# 2CAN.net
KiCad netlist of a schematic drawn in EAGLE
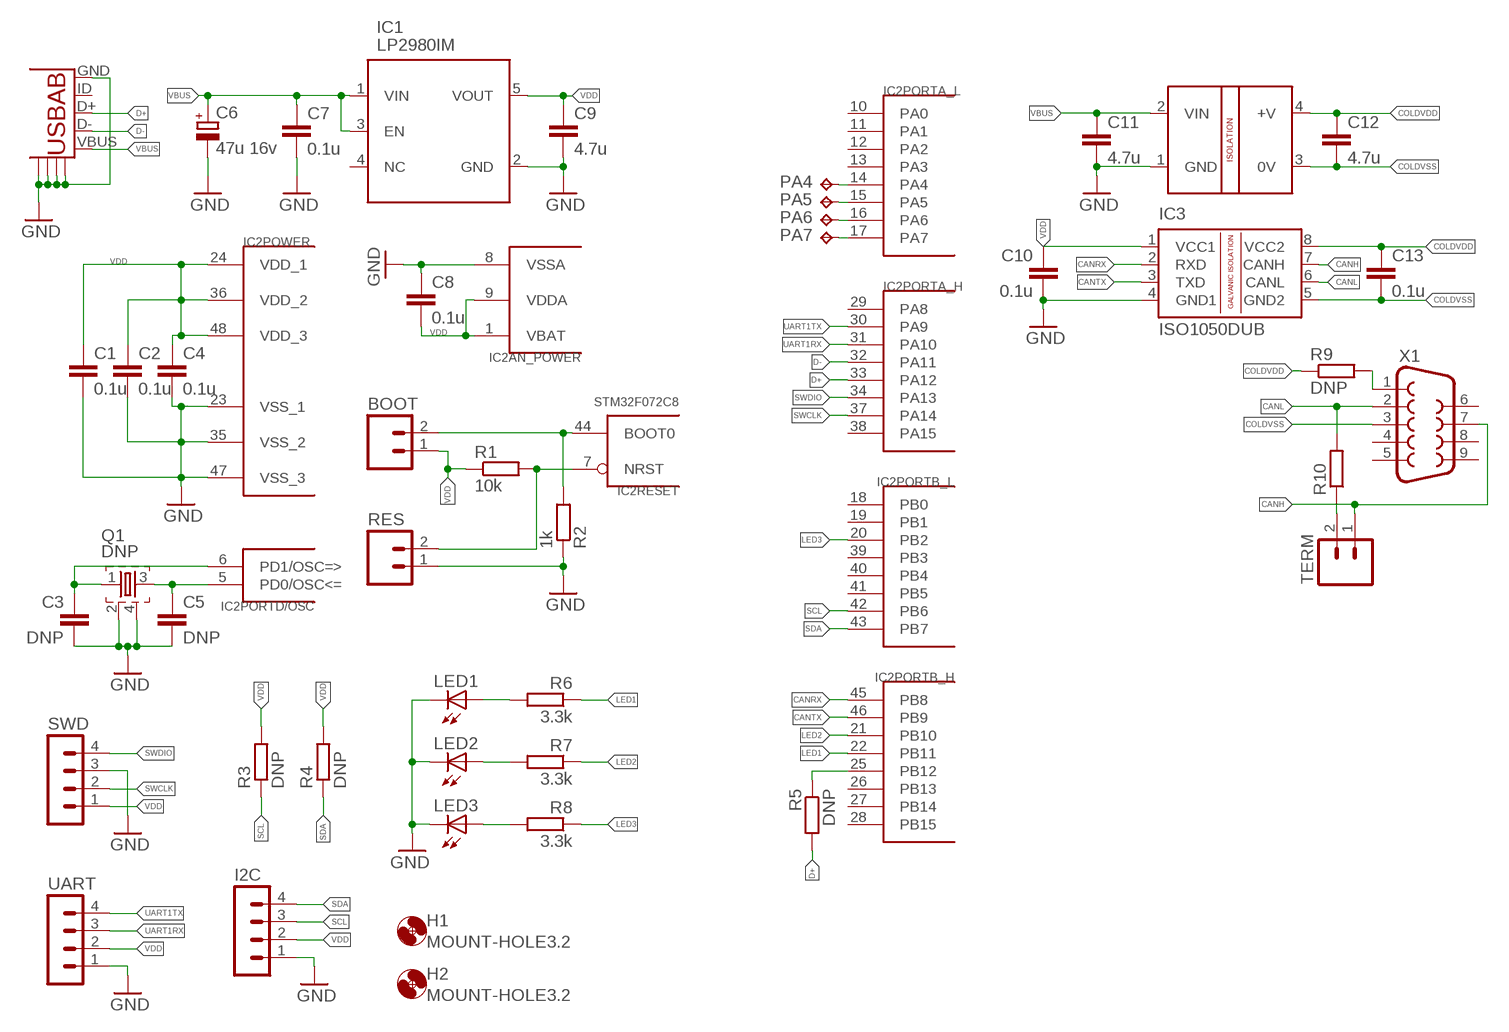
[diagram p0: schematic, sheet 1]

(export (version "E")
  (design (tool "Eeschema 10.0.6"))
  (components
    (comp (ref "BOOT")
      (value "M02PTH")
      (footprint "eagle-import:1X02")
      (libsource (lib "eagle-import") (part "M02PTH"))
    )
    (comp (ref "C1")
      (value "0.1u")
      (footprint "eagle-import:C0603")
      (libsource (lib "eagle-import") (part "C-EUC0603"))
    )
    (comp (ref "C2")
      (value "0.1u")
      (footprint "eagle-import:C0603")
      (libsource (lib "eagle-import") (part "C-EUC0603"))
    )
    (comp (ref "C3")
      (value "DNP")
      (footprint "eagle-import:C0603")
      (libsource (lib "eagle-import") (part "C-EUC0603"))
    )
    (comp (ref "C4")
      (value "0.1u")
      (footprint "eagle-import:C0603")
      (libsource (lib "eagle-import") (part "C-EUC0603"))
    )
    (comp (ref "C5")
      (value "DNP")
      (footprint "eagle-import:C0603")
      (libsource (lib "eagle-import") (part "C-EUC0603"))
    )
    (comp (ref "C6")
      (value "47u 16v")
      (footprint "eagle-import:E2-5")
      (libsource (lib "eagle-import") (part "CPOL-EUE2-5"))
    )
    (comp (ref "C7")
      (value "0.1u")
      (footprint "eagle-import:C0603")
      (libsource (lib "eagle-import") (part "C-EUC0603"))
    )
    (comp (ref "C8")
      (value "0.1u")
      (footprint "eagle-import:C0603")
      (libsource (lib "eagle-import") (part "C-EUC0603"))
    )
    (comp (ref "C9")
      (value "4.7u")
      (footprint "eagle-import:C0805")
      (libsource (lib "eagle-import") (part "C-EUC0805"))
    )
    (comp (ref "C10")
      (value "0.1u")
      (footprint "eagle-import:C0603")
      (libsource (lib "eagle-import") (part "C-EUC0603"))
    )
    (comp (ref "C11")
      (value "4.7u")
      (footprint "eagle-import:C0805")
      (libsource (lib "eagle-import") (part "C-EUC0805"))
    )
    (comp (ref "C12")
      (value "4.7u")
      (footprint "eagle-import:C0805")
      (libsource (lib "eagle-import") (part "C-EUC0805"))
    )
    (comp (ref "C13")
      (value "0.1u")
      (footprint "eagle-import:C0603")
      (libsource (lib "eagle-import") (part "C-EUC0603"))
    )
    (comp (ref "H1")
      (value "MOUNT-HOLE3.2")
      (footprint "eagle-import:3,2")
      (libsource (lib "eagle-import") (part "MOUNT-HOLE3.2"))
    )
    (comp (ref "H2")
      (value "MOUNT-HOLE3.2")
      (footprint "eagle-import:3,2")
      (libsource (lib "eagle-import") (part "MOUNT-HOLE3.2"))
    )
    (comp (ref "I2C")
      (value "MA04-1")
      (footprint "eagle-import:MA04-1")
      (libsource (lib "eagle-import") (part "MA04-1"))
    )
    (comp (ref "IC1")
      (value "LP2980IM")
      (footprint "eagle-import:SOT23-5L")
      (libsource (lib "eagle-import") (part "LP2980IM"))
    )
    (comp (ref "IC2")
      (value "STM32F072C8")
      (footprint "eagle-import:TQFP48")
      (libsource (lib "eagle-import") (part "STM32F10XCXT6"))
    )
    (comp (ref "IC3")
      (value "ISO1050DUB")
      (footprint "eagle-import:DUB-R-PDSO-G8")
      (fields (field (name "MPN") "ISO1050DUBR"))
      (libsource (lib "eagle-import") (part "ISO1050DUB"))
    )
    (comp (ref "LED1")
      (value "LEDSML0603")
      (footprint "eagle-import:SML0603")
      (libsource (lib "eagle-import") (part "LEDSML0603"))
    )
    (comp (ref "LED2")
      (value "LEDSML0603")
      (footprint "eagle-import:SML0603")
      (libsource (lib "eagle-import") (part "LEDSML0603"))
    )
    (comp (ref "LED3")
      (value "LEDSML0603")
      (footprint "eagle-import:SML0603")
      (libsource (lib "eagle-import") (part "LEDSML0603"))
    )
    (comp (ref "PA4")
      (value "TPB1,27")
      (footprint "eagle-import:B1,27")
      (libsource (lib "eagle-import") (part "TPB1,27"))
    )
    (comp (ref "PA5")
      (value "TPB1,27")
      (footprint "eagle-import:B1,27")
      (libsource (lib "eagle-import") (part "TPB1,27"))
    )
    (comp (ref "PA6")
      (value "TPB1,27")
      (footprint "eagle-import:B1,27")
      (libsource (lib "eagle-import") (part "TPB1,27"))
    )
    (comp (ref "PA7")
      (value "TPB1,27")
      (footprint "eagle-import:B1,27")
      (libsource (lib "eagle-import") (part "TPB1,27"))
    )
    (comp (ref "Q1")
      (value "DNP")
      (footprint "eagle-import:FA-20H")
      (libsource (lib "eagle-import") (part "FA-3225"))
    )
    (comp (ref "R1")
      (value "10k")
      (footprint "eagle-import:R0603")
      (libsource (lib "eagle-import") (part "R-EU_R0603"))
    )
    (comp (ref "R2")
      (value "1k")
      (footprint "eagle-import:R0603")
      (libsource (lib "eagle-import") (part "R-EU_R0603"))
    )
    (comp (ref "R3")
      (value "DNP")
      (footprint "eagle-import:R0603")
      (libsource (lib "eagle-import") (part "R-EU_R0603"))
    )
    (comp (ref "R4")
      (value "DNP")
      (footprint "eagle-import:R0603")
      (libsource (lib "eagle-import") (part "R-EU_R0603"))
    )
    (comp (ref "R5")
      (value "DNP")
      (footprint "eagle-import:R0603")
      (libsource (lib "eagle-import") (part "R-EU_R0603"))
    )
    (comp (ref "R6")
      (value "3.3k")
      (footprint "eagle-import:R0603")
      (libsource (lib "eagle-import") (part "R-EU_R0603"))
    )
    (comp (ref "R7")
      (value "3.3k")
      (footprint "eagle-import:R0603")
      (libsource (lib "eagle-import") (part "R-EU_R0603"))
    )
    (comp (ref "R8")
      (value "3.3k")
      (footprint "eagle-import:R0603")
      (libsource (lib "eagle-import") (part "R-EU_R0603"))
    )
    (comp (ref "R9")
      (value "DNP")
      (footprint "eagle-import:R0805")
      (libsource (lib "eagle-import") (part "R-EU_R0805"))
    )
    (comp (ref "R10")
      (value "R-EU_R0805")
      (footprint "eagle-import:R0805")
      (libsource (lib "eagle-import") (part "R-EU_R0805"))
    )
    (comp (ref "RES")
      (value "M02PTH")
      (footprint "eagle-import:1X02")
      (libsource (lib "eagle-import") (part "M02PTH"))
    )
    (comp (ref "SWD")
      (value "MA04-1")
      (footprint "eagle-import:MA04-1")
      (libsource (lib "eagle-import") (part "MA04-1"))
    )
    (comp (ref "TERM")
      (value "M02PTH")
      (footprint "eagle-import:1X02")
      (libsource (lib "eagle-import") (part "M02PTH"))
    )
    (comp (ref "U$1")
      (value "USB_AB")
      (footprint "eagle-import:USB-AB-MICRO-SMD")
      (libsource (lib "eagle-import") (part "USB_AB"))
    )
    (comp (ref "U$2")
      (value "B0505SV")
      (footprint "eagle-import:B0505S_V")
      (libsource (lib "eagle-import") (part "B0505SV"))
    )
    (comp (ref "UART")
      (value "MA04-1")
      (footprint "eagle-import:MA04-1")
      (libsource (lib "eagle-import") (part "MA04-1"))
    )
    (comp (ref "X1")
      (value "DB9MALE")
      (footprint "eagle-import:DB9_MALE")
      (libsource (lib "eagle-import") (part "DB9MALE"))
    )
  )
  (nets
    (net (code "1") (name "CANH") (class "Default")
      (node (ref "IC3") (pin "7") (pinfunction "CANH_7") (pintype "input"))
      (node (ref "TERM") (pin "1") (pinfunction "1_1") (pintype "passive"))
      (node (ref "X1") (pin "7") (pinfunction "7_7") (pintype "passive"))
    )
    (net (code "2") (name "CANL") (class "Default")
      (node (ref "IC3") (pin "6") (pinfunction "CANL_6") (pintype "input"))
      (node (ref "R10") (pin "2") (pinfunction "2_2") (pintype "passive"))
      (node (ref "X1") (pin "2") (pinfunction "2_2") (pintype "passive"))
    )
    (net (code "3") (name "CANRX") (class "Default")
      (node (ref "IC2") (pin "45") (pinfunction "PB8_45") (pintype "bidirectional"))
      (node (ref "IC3") (pin "2") (pinfunction "RXD_2") (pintype "input"))
    )
    (net (code "4") (name "CANTX") (class "Default")
      (node (ref "IC2") (pin "46") (pinfunction "PB9_46") (pintype "bidirectional"))
      (node (ref "IC3") (pin "3") (pinfunction "TXD_3") (pintype "input"))
    )
    (net (code "5") (name "COLDVDD") (class "Default")
      (node (ref "C12") (pin "1") (pinfunction "1_1") (pintype "passive"))
      (node (ref "C13") (pin "1") (pinfunction "1_1") (pintype "passive"))
      (node (ref "IC3") (pin "8") (pinfunction "VCC2_8") (pintype "input"))
      (node (ref "R9") (pin "1") (pinfunction "1_1") (pintype "passive"))
      (node (ref "U$2") (pin "4") (pinfunction "+V_4") (pintype "power_in"))
    )
    (net (code "6") (name "COLDVSS") (class "Default")
      (node (ref "C12") (pin "2") (pinfunction "2_2") (pintype "passive"))
      (node (ref "C13") (pin "2") (pinfunction "2_2") (pintype "passive"))
      (node (ref "IC3") (pin "5") (pinfunction "GND2_5") (pintype "input"))
      (node (ref "U$2") (pin "3") (pinfunction "0V_3") (pintype "power_in"))
      (node (ref "X1") (pin "3") (pinfunction "3_3") (pintype "passive"))
    )
    (net (code "7") (name "D+") (class "Default")
      (node (ref "IC2") (pin "33") (pinfunction "PA12_33") (pintype "bidirectional"))
      (node (ref "R5") (pin "2") (pinfunction "2_2") (pintype "passive"))
      (node (ref "U$1") (pin "D+") (pinfunction "D+_D+") (pintype "bidirectional"))
    )
    (net (code "8") (name "D-") (class "Default")
      (node (ref "IC2") (pin "32") (pinfunction "PA11_32") (pintype "bidirectional"))
      (node (ref "U$1") (pin "D-") (pinfunction "D-_D-") (pintype "bidirectional"))
    )
    (net (code "9") (name "GND") (class "Default")
      (node (ref "C1") (pin "2") (pinfunction "2_2") (pintype "passive"))
      (node (ref "C10") (pin "2") (pinfunction "2_2") (pintype "passive"))
      (node (ref "C11") (pin "2") (pinfunction "2_2") (pintype "passive"))
      (node (ref "C2") (pin "2") (pinfunction "2_2") (pintype "passive"))
      (node (ref "C3") (pin "2") (pinfunction "2_2") (pintype "passive"))
      (node (ref "C4") (pin "2") (pinfunction "2_2") (pintype "passive"))
      (node (ref "C5") (pin "2") (pinfunction "2_2") (pintype "passive"))
      (node (ref "C6") (pin "-") (pinfunction "-_-") (pintype "passive"))
      (node (ref "C7") (pin "2") (pinfunction "2_2") (pintype "passive"))
      (node (ref "C8") (pin "1") (pinfunction "1_1") (pintype "passive"))
      (node (ref "C9") (pin "2") (pinfunction "2_2") (pintype "passive"))
      (node (ref "I2C") (pin "1") (pinfunction "1_1") (pintype "passive"))
      (node (ref "IC1") (pin "2") (pinfunction "GND_2") (pintype "power_in"))
      (node (ref "IC2") (pin "23") (pinfunction "VSS_1_23") (pintype "power_in"))
      (node (ref "IC2") (pin "35") (pinfunction "VSS_2_35") (pintype "power_in"))
      (node (ref "IC2") (pin "47") (pinfunction "VSS_3_47") (pintype "power_in"))
      (node (ref "IC2") (pin "8") (pinfunction "VSSA_8") (pintype "power_in"))
      (node (ref "IC3") (pin "4") (pinfunction "GND1_4") (pintype "input"))
      (node (ref "LED1") (pin "C") (pinfunction "C_C") (pintype "passive"))
      (node (ref "LED2") (pin "C") (pinfunction "C_C") (pintype "passive"))
      (node (ref "LED3") (pin "C") (pinfunction "C_C") (pintype "passive"))
      (node (ref "Q1") (pin "2") (pinfunction "2_2") (pintype "passive"))
      (node (ref "Q1") (pin "4") (pinfunction "4_4") (pintype "passive"))
      (node (ref "R2") (pin "1") (pinfunction "1_1") (pintype "passive"))
      (node (ref "RES") (pin "1") (pinfunction "1_1") (pintype "passive"))
      (node (ref "SWD") (pin "3") (pinfunction "3_3") (pintype "passive"))
      (node (ref "U$1") (pin "GND") (pinfunction "GND_GND") (pintype "power_in"))
      (node (ref "U$1") (pin "GND@1") (pinfunction "P$1_GND@1") (pintype "power_in"))
      (node (ref "U$1") (pin "GND@2") (pinfunction "P$2_GND@2") (pintype "power_in"))
      (node (ref "U$1") (pin "GND@3") (pinfunction "P$3_GND@3") (pintype "power_in"))
      (node (ref "U$1") (pin "GND@4") (pinfunction "P$4_GND@4") (pintype "power_in"))
      (node (ref "U$2") (pin "1") (pinfunction "GND_1") (pintype "power_in"))
      (node (ref "UART") (pin "1") (pinfunction "1_1") (pintype "passive"))
    )
    (net (code "10") (name "LED1") (class "Default")
      (node (ref "IC2") (pin "22") (pinfunction "PB11_22") (pintype "bidirectional"))
      (node (ref "R6") (pin "1") (pinfunction "1_1") (pintype "passive"))
    )
    (net (code "11") (name "LED2") (class "Default")
      (node (ref "IC2") (pin "21") (pinfunction "PB10_21") (pintype "bidirectional"))
      (node (ref "R7") (pin "1") (pinfunction "1_1") (pintype "passive"))
    )
    (net (code "12") (name "LED3") (class "Default")
      (node (ref "IC2") (pin "20") (pinfunction "PB2_20") (pintype "bidirectional"))
      (node (ref "R8") (pin "1") (pinfunction "1_1") (pintype "passive"))
    )
    (net (code "13") (name "Net-(IC2C-PA4)") (class "Default")
      (node (ref "IC2") (pin "14") (pinfunction "PA4_14") (pintype "bidirectional"))
      (node (ref "PA4") (pin "TP") (pinfunction "TP_TP") (pintype "input"))
    )
    (net (code "14") (name "Net-(IC2C-PA5)") (class "Default")
      (node (ref "IC2") (pin "15") (pinfunction "PA5_15") (pintype "bidirectional"))
      (node (ref "PA5") (pin "TP") (pinfunction "TP_TP") (pintype "input"))
    )
    (net (code "15") (name "Net-(IC2C-PA6)") (class "Default")
      (node (ref "IC2") (pin "16") (pinfunction "PA6_16") (pintype "bidirectional"))
      (node (ref "PA6") (pin "TP") (pinfunction "TP_TP") (pintype "input"))
    )
    (net (code "16") (name "Net-(IC2C-PA7)") (class "Default")
      (node (ref "IC2") (pin "17") (pinfunction "PA7_17") (pintype "bidirectional"))
      (node (ref "PA7") (pin "TP") (pinfunction "TP_TP") (pintype "input"))
    )
    (net (code "17") (name "Net-(IC2D-PB12)") (class "Default")
      (node (ref "IC2") (pin "25") (pinfunction "PB12_25") (pintype "bidirectional"))
      (node (ref "R5") (pin "1") (pinfunction "1_1") (pintype "passive"))
    )
    (net (code "18") (name "Net-(IC2G-PD0{slash}OSC<=)") (class "Default")
      (node (ref "C5") (pin "1") (pinfunction "1_1") (pintype "passive"))
      (node (ref "IC2") (pin "5") (pinfunction "PD0/OSC<=_5") (pintype "bidirectional"))
      (node (ref "Q1") (pin "3") (pinfunction "3_3") (pintype "passive"))
    )
    (net (code "19") (name "Net-(IC2G-PD1{slash}OSC=>)") (class "Default")
      (node (ref "C3") (pin "1") (pinfunction "1_1") (pintype "passive"))
      (node (ref "IC2") (pin "6") (pinfunction "PD1/OSC=>_6") (pintype "bidirectional"))
      (node (ref "Q1") (pin "1") (pinfunction "1_1") (pintype "passive"))
    )
    (net (code "20") (name "Net-(IC2I-BOOT0)") (class "Default")
      (node (ref "BOOT") (pin "2") (pinfunction "2_2") (pintype "passive"))
      (node (ref "IC2") (pin "44") (pinfunction "BOOT0_44") (pintype "input"))
      (node (ref "R2") (pin "2") (pinfunction "2_2") (pintype "passive"))
    )
    (net (code "21") (name "Net-(IC2I-NRST)") (class "Default")
      (node (ref "IC2") (pin "7") (pinfunction "NRST_7") (pintype "input"))
      (node (ref "R1") (pin "2") (pinfunction "2_2") (pintype "passive"))
      (node (ref "RES") (pin "2") (pinfunction "2_2") (pintype "passive"))
    )
    (net (code "22") (name "Net-(LED1-PadA)") (class "Default")
      (node (ref "LED1") (pin "A") (pinfunction "A_A") (pintype "passive"))
      (node (ref "R6") (pin "2") (pinfunction "2_2") (pintype "passive"))
    )
    (net (code "23") (name "Net-(LED2-PadA)") (class "Default")
      (node (ref "LED2") (pin "A") (pinfunction "A_A") (pintype "passive"))
      (node (ref "R7") (pin "2") (pinfunction "2_2") (pintype "passive"))
    )
    (net (code "24") (name "Net-(LED3-PadA)") (class "Default")
      (node (ref "LED3") (pin "A") (pinfunction "A_A") (pintype "passive"))
      (node (ref "R8") (pin "2") (pinfunction "2_2") (pintype "passive"))
    )
    (net (code "25") (name "Net-(R9-Pad2)") (class "Default")
      (node (ref "R9") (pin "2") (pinfunction "2_2") (pintype "passive"))
      (node (ref "X1") (pin "1") (pinfunction "1_1") (pintype "passive"))
    )
    (net (code "26") (name "Net-(R10-Pad1)") (class "Default")
      (node (ref "R10") (pin "1") (pinfunction "1_1") (pintype "passive"))
      (node (ref "TERM") (pin "2") (pinfunction "2_2") (pintype "passive"))
    )
    (net (code "27") (name "SCL") (class "Default")
      (node (ref "I2C") (pin "3") (pinfunction "3_3") (pintype "passive"))
      (node (ref "IC2") (pin "42") (pinfunction "PB6_42") (pintype "bidirectional"))
      (node (ref "R3") (pin "1") (pinfunction "1_1") (pintype "passive"))
    )
    (net (code "28") (name "SDA") (class "Default")
      (node (ref "I2C") (pin "4") (pinfunction "4_4") (pintype "passive"))
      (node (ref "IC2") (pin "43") (pinfunction "PB7_43") (pintype "bidirectional"))
      (node (ref "R4") (pin "1") (pinfunction "1_1") (pintype "passive"))
    )
    (net (code "29") (name "SWCLK") (class "Default")
      (node (ref "IC2") (pin "37") (pinfunction "PA14_37") (pintype "bidirectional"))
      (node (ref "SWD") (pin "2") (pinfunction "2_2") (pintype "passive"))
    )
    (net (code "30") (name "SWDIO") (class "Default")
      (node (ref "IC2") (pin "34") (pinfunction "PA13_34") (pintype "bidirectional"))
      (node (ref "SWD") (pin "4") (pinfunction "4_4") (pintype "passive"))
    )
    (net (code "31") (name "UART1RX") (class "Default")
      (node (ref "IC2") (pin "31") (pinfunction "PA10_31") (pintype "bidirectional"))
      (node (ref "UART") (pin "3") (pinfunction "3_3") (pintype "passive"))
    )
    (net (code "32") (name "UART1TX") (class "Default")
      (node (ref "IC2") (pin "30") (pinfunction "PA9_30") (pintype "bidirectional"))
      (node (ref "UART") (pin "4") (pinfunction "4_4") (pintype "passive"))
    )
    (net (code "33") (name "VBUS") (class "Default")
      (node (ref "C11") (pin "1") (pinfunction "1_1") (pintype "passive"))
      (node (ref "C6") (pin "+") (pinfunction "+_+") (pintype "passive"))
      (node (ref "C7") (pin "1") (pinfunction "1_1") (pintype "passive"))
      (node (ref "IC1") (pin "1") (pinfunction "VIN_1") (pintype "power_in"))
      (node (ref "IC1") (pin "3") (pinfunction "EN_3") (pintype "input"))
      (node (ref "U$1") (pin "VBUS") (pinfunction "VBUS_VBUS") (pintype "power_in"))
      (node (ref "U$2") (pin "2") (pinfunction "VIN_2") (pintype "power_in"))
    )
    (net (code "34") (name "VDD") (class "Default")
      (node (ref "BOOT") (pin "1") (pinfunction "1_1") (pintype "passive"))
      (node (ref "C1") (pin "1") (pinfunction "1_1") (pintype "passive"))
      (node (ref "C10") (pin "1") (pinfunction "1_1") (pintype "passive"))
      (node (ref "C2") (pin "1") (pinfunction "1_1") (pintype "passive"))
      (node (ref "C4") (pin "1") (pinfunction "1_1") (pintype "passive"))
      (node (ref "C8") (pin "2") (pinfunction "2_2") (pintype "passive"))
      (node (ref "C9") (pin "1") (pinfunction "1_1") (pintype "passive"))
      (node (ref "I2C") (pin "2") (pinfunction "2_2") (pintype "passive"))
      (node (ref "IC1") (pin "5") (pinfunction "VOUT_5") (pintype "power_in"))
      (node (ref "IC2") (pin "1") (pinfunction "VBAT_1") (pintype "power_in"))
      (node (ref "IC2") (pin "24") (pinfunction "VDD_1_24") (pintype "power_in"))
      (node (ref "IC2") (pin "36") (pinfunction "VDD_2_36") (pintype "power_in"))
      (node (ref "IC2") (pin "48") (pinfunction "VDD_3_48") (pintype "power_in"))
      (node (ref "IC2") (pin "9") (pinfunction "VDDA_9") (pintype "power_in"))
      (node (ref "IC3") (pin "1") (pinfunction "VCC1_1") (pintype "input"))
      (node (ref "R1") (pin "1") (pinfunction "1_1") (pintype "passive"))
      (node (ref "R3") (pin "2") (pinfunction "2_2") (pintype "passive"))
      (node (ref "R4") (pin "2") (pinfunction "2_2") (pintype "passive"))
      (node (ref "SWD") (pin "1") (pinfunction "1_1") (pintype "passive"))
      (node (ref "UART") (pin "2") (pinfunction "2_2") (pintype "passive"))
    )
    (net (code "35") (name "unconnected-(IC1-NC-Pad4)") (class "Default")
      (node (ref "IC1") (pin "4") (pinfunction "NC_4") (pintype "no_connect"))
    )
    (net (code "36") (name "unconnected-(IC2B-PA8-Pad29)") (class "Default")
      (node (ref "IC2") (pin "29") (pinfunction "PA8_29") (pintype "bidirectional"))
    )
    (net (code "37") (name "unconnected-(IC2B-PA15-Pad38)") (class "Default")
      (node (ref "IC2") (pin "38") (pinfunction "PA15_38") (pintype "bidirectional"))
    )
    (net (code "38") (name "unconnected-(IC2C-PA0-Pad10)") (class "Default")
      (node (ref "IC2") (pin "10") (pinfunction "PA0_10") (pintype "bidirectional"))
    )
    (net (code "39") (name "unconnected-(IC2C-PA1-Pad11)") (class "Default")
      (node (ref "IC2") (pin "11") (pinfunction "PA1_11") (pintype "bidirectional"))
    )
    (net (code "40") (name "unconnected-(IC2C-PA2-Pad12)") (class "Default")
      (node (ref "IC2") (pin "12") (pinfunction "PA2_12") (pintype "bidirectional"))
    )
    (net (code "41") (name "unconnected-(IC2C-PA3-Pad13)") (class "Default")
      (node (ref "IC2") (pin "13") (pinfunction "PA3_13") (pintype "bidirectional"))
    )
    (net (code "42") (name "unconnected-(IC2D-PB13-Pad26)") (class "Default")
      (node (ref "IC2") (pin "26") (pinfunction "PB13_26") (pintype "bidirectional"))
    )
    (net (code "43") (name "unconnected-(IC2D-PB14-Pad27)") (class "Default")
      (node (ref "IC2") (pin "27") (pinfunction "PB14_27") (pintype "bidirectional"))
    )
    (net (code "44") (name "unconnected-(IC2D-PB15-Pad28)") (class "Default")
      (node (ref "IC2") (pin "28") (pinfunction "PB15_28") (pintype "bidirectional"))
    )
    (net (code "45") (name "unconnected-(IC2E-PB0-Pad18)") (class "Default")
      (node (ref "IC2") (pin "18") (pinfunction "PB0_18") (pintype "bidirectional"))
    )
    (net (code "46") (name "unconnected-(IC2E-PB1-Pad19)") (class "Default")
      (node (ref "IC2") (pin "19") (pinfunction "PB1_19") (pintype "bidirectional"))
    )
    (net (code "47") (name "unconnected-(IC2E-PB3-Pad39)") (class "Default")
      (node (ref "IC2") (pin "39") (pinfunction "PB3_39") (pintype "bidirectional"))
    )
    (net (code "48") (name "unconnected-(IC2E-PB4-Pad40)") (class "Default")
      (node (ref "IC2") (pin "40") (pinfunction "PB4_40") (pintype "bidirectional"))
    )
    (net (code "49") (name "unconnected-(IC2E-PB5-Pad41)") (class "Default")
      (node (ref "IC2") (pin "41") (pinfunction "PB5_41") (pintype "bidirectional"))
    )
    (net (code "50") (name "unconnected-(U$1-USBID-PadID)") (class "Default")
      (node (ref "U$1") (pin "ID") (pinfunction "USBID_ID") (pintype "bidirectional"))
    )
    (net (code "51") (name "unconnected-(X1-Pad4)") (class "Default")
      (node (ref "X1") (pin "4") (pinfunction "4_4") (pintype "passive"))
    )
    (net (code "52") (name "unconnected-(X1-Pad5)") (class "Default")
      (node (ref "X1") (pin "5") (pinfunction "5_5") (pintype "passive"))
    )
    (net (code "53") (name "unconnected-(X1-Pad6)") (class "Default")
      (node (ref "X1") (pin "6") (pinfunction "6_6") (pintype "passive"))
    )
    (net (code "54") (name "unconnected-(X1-Pad8)") (class "Default")
      (node (ref "X1") (pin "8") (pinfunction "8_8") (pintype "passive"))
    )
    (net (code "55") (name "unconnected-(X1-Pad9)") (class "Default")
      (node (ref "X1") (pin "9") (pinfunction "9_9") (pintype "passive"))
    )
  )
)
